# SparkFun_Tri_Axis_Accel_Breakout-H3LIS33.net
KiCad netlist of a schematic drawn in EAGLE
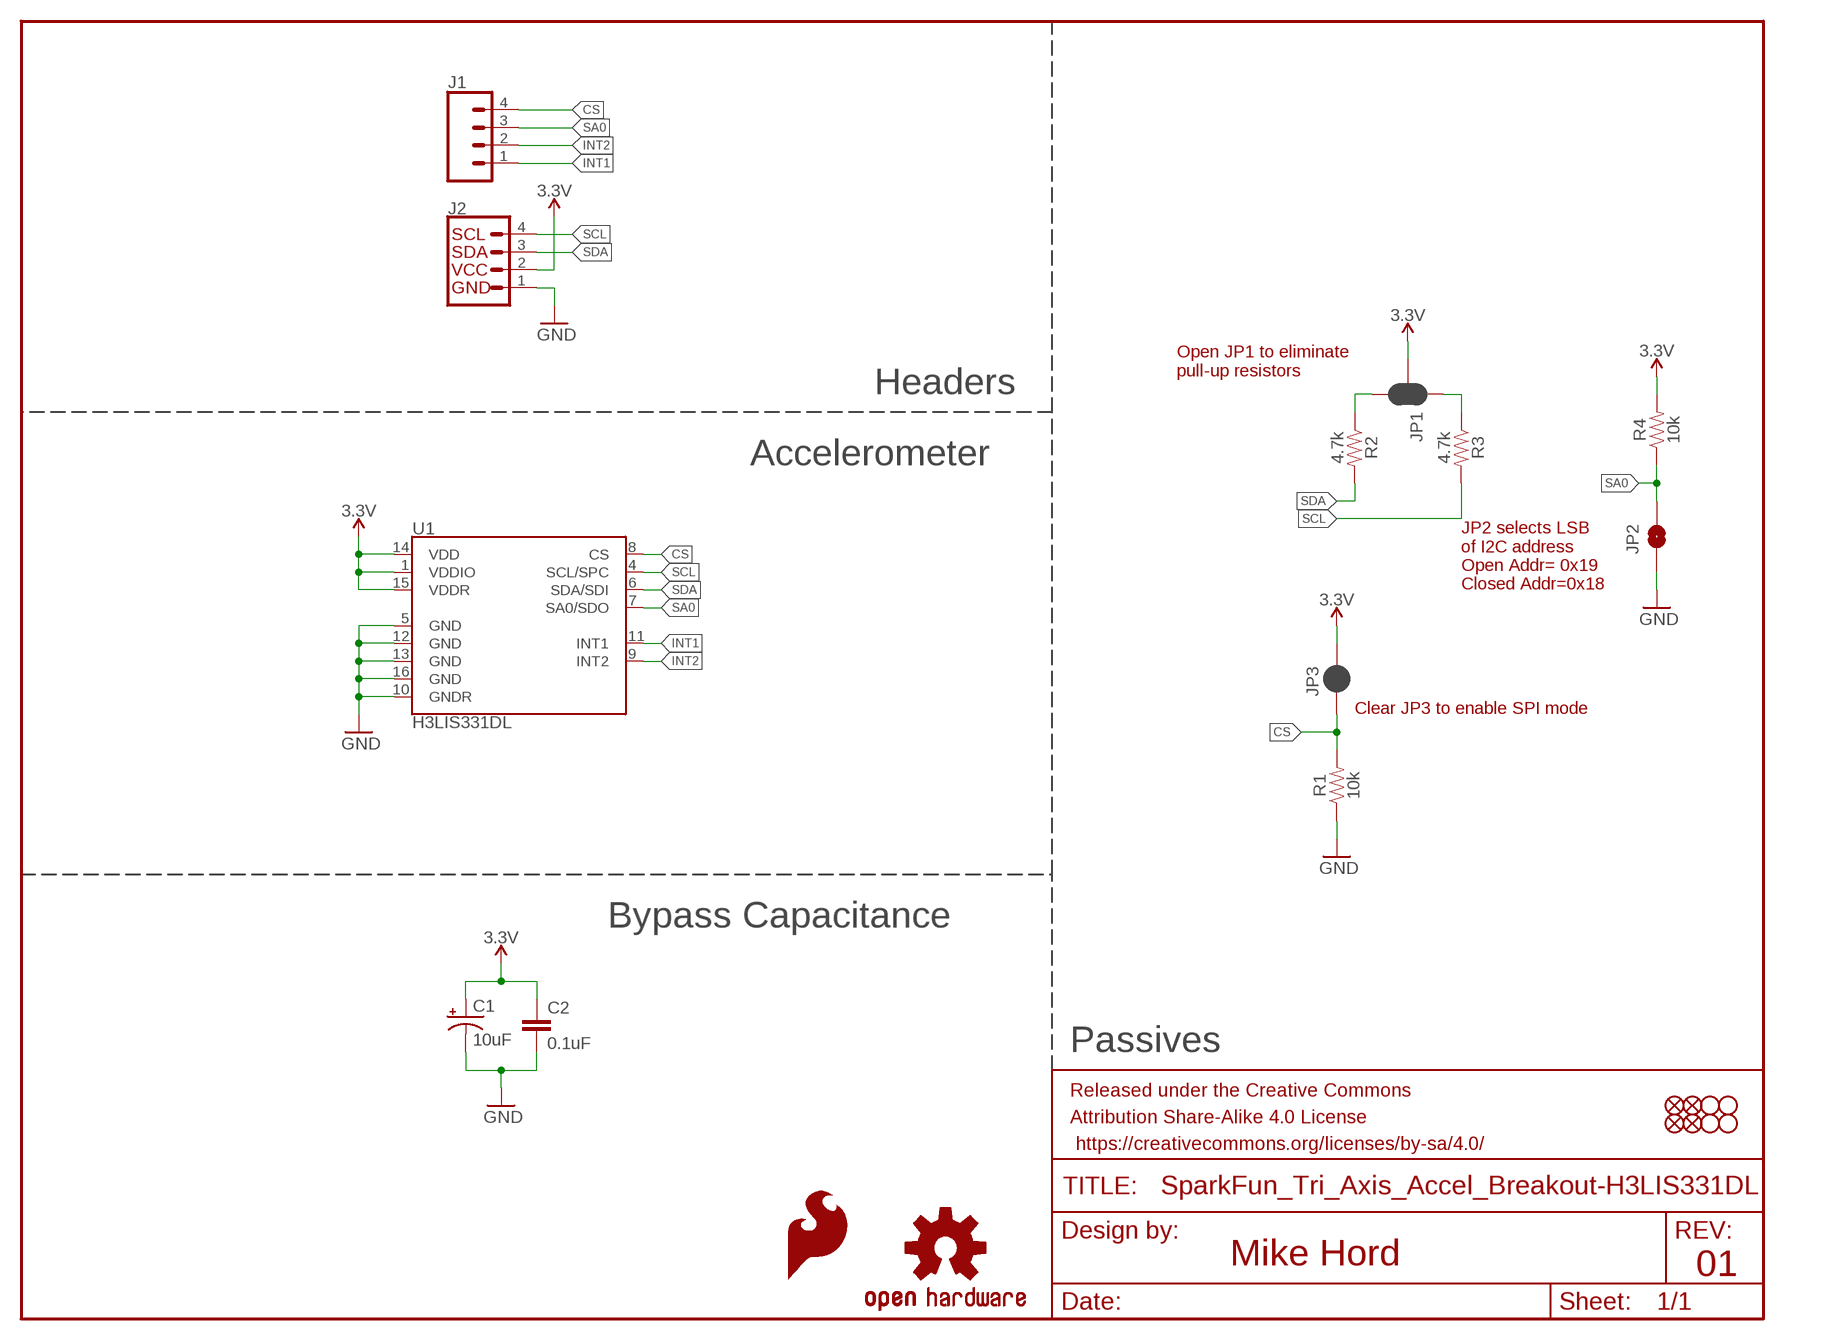
[diagram p0: schematic, sheet 1]

(export (version "E")
  (design (tool "Eeschema 10.0.6"))
  (components
    (comp (ref "C1")
      (value "10uF")
      (footprint "eagle-import:EIA3216")
      (libsource (lib "eagle-import") (part "10UF-POLAR-EIA3216-16V-10%(TANT)"))
    )
    (comp (ref "C2")
      (value "0.1uF")
      (footprint "eagle-import:0603")
      (libsource (lib "eagle-import") (part "0.1UF-0603-25V-5%"))
    )
    (comp (ref "FRAME1")
      (value "FRAME-LETTER")
      (footprint "eagle-import:CREATIVE_COMMONS")
      (libsource (lib "eagle-import") (part "FRAME-LETTER"))
    )
    (comp (ref "J1")
      (value "CONN_04")
      (footprint "eagle-import:1X04")
      (libsource (lib "eagle-import") (part "CONN_04"))
    )
    (comp (ref "J2")
      (value "I2C_STANDARD")
      (footprint "eagle-import:1X04")
      (libsource (lib "eagle-import") (part "I2C_STANDARD"))
    )
    (comp (ref "JP1")
      (value "JUMPER-SMT_3_2-NC_PASTE_NO-SILK")
      (footprint "eagle-import:SMT-JUMPER_3_2-NC_PASTE_NO-SILK")
      (libsource (lib "eagle-import") (part "JUMPER-SMT_3_2-NC_PASTE_NO-SILK"))
    )
    (comp (ref "JP2")
      (value "JUMPER-SMT_2_NO_NO-SILK")
      (footprint "eagle-import:SMT-JUMPER_2_NO_NO-SILK")
      (libsource (lib "eagle-import") (part "JUMPER-SMT_2_NO_NO-SILK"))
    )
    (comp (ref "JP3")
      (value "JUMPER-SMT_2_NC_PASTE_NO-SILK")
      (footprint "eagle-import:SMT-JUMPER_2_NC_PASTE_NO-SILK")
      (libsource (lib "eagle-import") (part "JUMPER-SMT_2_NC_PASTE_NO-SILK"))
    )
    (comp (ref "JP4")
      (value "FIDUCIAL1X2")
      (footprint "eagle-import:FIDUCIAL-1X2")
      (libsource (lib "eagle-import") (part "FIDUCIAL1X2"))
    )
    (comp (ref "JP5")
      (value "FIDUCIAL1X2")
      (footprint "eagle-import:FIDUCIAL-1X2")
      (libsource (lib "eagle-import") (part "FIDUCIAL1X2"))
    )
    (comp (ref "JP6")
      (value "FIDUCIAL1X2")
      (footprint "eagle-import:FIDUCIAL-1X2")
      (libsource (lib "eagle-import") (part "FIDUCIAL1X2"))
    )
    (comp (ref "JP7")
      (value "FIDUCIAL1X2")
      (footprint "eagle-import:FIDUCIAL-1X2")
      (libsource (lib "eagle-import") (part "FIDUCIAL1X2"))
    )
    (comp (ref "JP8")
      (value "STAND-OFF")
      (footprint "eagle-import:STAND-OFF")
      (libsource (lib "eagle-import") (part "STAND-OFF"))
    )
    (comp (ref "JP9")
      (value "STAND-OFF")
      (footprint "eagle-import:STAND-OFF")
      (libsource (lib "eagle-import") (part "STAND-OFF"))
    )
    (comp (ref "JP10")
      (value "STAND-OFF")
      (footprint "eagle-import:STAND-OFF")
      (libsource (lib "eagle-import") (part "STAND-OFF"))
    )
    (comp (ref "JP11")
      (value "STAND-OFF")
      (footprint "eagle-import:STAND-OFF")
      (libsource (lib "eagle-import") (part "STAND-OFF"))
    )
    (comp (ref "LOGO1")
      (value "SFE_LOGO_FLAME.1_INCH")
      (footprint "eagle-import:SFE_LOGO_FLAME_.1")
      (libsource (lib "eagle-import") (part "SFE_LOGO_FLAME.1_INCH"))
    )
    (comp (ref "LOGO2")
      (value "OSHW-LOGOS")
      (footprint "eagle-import:OSHW-LOGO-S")
      (libsource (lib "eagle-import") (part "OSHW-LOGOS"))
    )
    (comp (ref "R1")
      (value "10k")
      (footprint "eagle-import:0603")
      (libsource (lib "eagle-import") (part "10KOHM-0603-1/10W-1%"))
    )
    (comp (ref "R2")
      (value "4.7k")
      (footprint "eagle-import:0603")
      (libsource (lib "eagle-import") (part "4.7KOHM-0603-1/10W-1%"))
    )
    (comp (ref "R3")
      (value "4.7k")
      (footprint "eagle-import:0603")
      (libsource (lib "eagle-import") (part "4.7KOHM-0603-1/10W-1%"))
    )
    (comp (ref "R4")
      (value "10k")
      (footprint "eagle-import:0603")
      (libsource (lib "eagle-import") (part "10KOHM-0603-1/10W-1%"))
    )
    (comp (ref "U1")
      (value "H3LIS331DL")
      (footprint "eagle-import:LGA-16-3X3")
      (libsource (lib "eagle-import") (part "H3LIS331DL"))
    )
  )
  (nets
    (net (code "1") (name "3.3V") (class "Default")
      (node (ref "C1") (pin "+") (pinfunction "+_+") (pintype "passive"))
      (node (ref "C2") (pin "1") (pinfunction "1_1") (pintype "passive"))
      (node (ref "J2") (pin "2") (pinfunction "2_2") (pintype "power_in"))
      (node (ref "JP1") (pin "2") (pinfunction "2_2") (pintype "passive"))
      (node (ref "JP3") (pin "2") (pinfunction "2_2") (pintype "passive"))
      (node (ref "R4") (pin "2") (pinfunction "2_2") (pintype "passive"))
      (node (ref "U1") (pin "1") (pinfunction "VDDIO_1") (pintype "bidirectional"))
      (node (ref "U1") (pin "14") (pinfunction "VDD_14") (pintype "bidirectional"))
      (node (ref "U1") (pin "15") (pinfunction "VDDR_15") (pintype "bidirectional"))
    )
    (net (code "2") (name "CS") (class "Default")
      (node (ref "J1") (pin "4") (pinfunction "4_4") (pintype "passive"))
      (node (ref "JP3") (pin "1") (pinfunction "1_1") (pintype "passive"))
      (node (ref "R1") (pin "2") (pinfunction "2_2") (pintype "passive"))
      (node (ref "U1") (pin "8") (pinfunction "CS_8") (pintype "bidirectional"))
    )
    (net (code "3") (name "GND") (class "Default")
      (node (ref "C1") (pin "-") (pinfunction "-_-") (pintype "passive"))
      (node (ref "C2") (pin "2") (pinfunction "2_2") (pintype "passive"))
      (node (ref "J2") (pin "1") (pinfunction "1_1") (pintype "power_in"))
      (node (ref "JP2") (pin "1") (pinfunction "1_1") (pintype "passive"))
      (node (ref "R1") (pin "1") (pinfunction "1_1") (pintype "passive"))
      (node (ref "U1") (pin "10") (pinfunction "GNDR_10") (pintype "bidirectional"))
      (node (ref "U1") (pin "12") (pinfunction "GND_12") (pintype "bidirectional"))
      (node (ref "U1") (pin "13") (pinfunction "GND_13") (pintype "bidirectional"))
      (node (ref "U1") (pin "16") (pinfunction "GND_16") (pintype "bidirectional"))
      (node (ref "U1") (pin "5") (pinfunction "GND_5") (pintype "bidirectional"))
    )
    (net (code "4") (name "INT1") (class "Default")
      (node (ref "J1") (pin "1") (pinfunction "1_1") (pintype "passive"))
      (node (ref "U1") (pin "11") (pinfunction "INT1_11") (pintype "bidirectional"))
    )
    (net (code "5") (name "INT2") (class "Default")
      (node (ref "J1") (pin "2") (pinfunction "2_2") (pintype "passive"))
      (node (ref "U1") (pin "9") (pinfunction "INT2_9") (pintype "bidirectional"))
    )
    (net (code "6") (name "Net-(JP1-Pad1)") (class "Default")
      (node (ref "JP1") (pin "1") (pinfunction "1_1") (pintype "passive"))
      (node (ref "R3") (pin "1") (pinfunction "1_1") (pintype "passive"))
    )
    (net (code "7") (name "Net-(JP1-Pad3)") (class "Default")
      (node (ref "JP1") (pin "3") (pinfunction "3_3") (pintype "passive"))
      (node (ref "R2") (pin "1") (pinfunction "1_1") (pintype "passive"))
    )
    (net (code "8") (name "SA0") (class "Default")
      (node (ref "J1") (pin "3") (pinfunction "3_3") (pintype "passive"))
      (node (ref "JP2") (pin "2") (pinfunction "2_2") (pintype "passive"))
      (node (ref "R4") (pin "1") (pinfunction "1_1") (pintype "passive"))
      (node (ref "U1") (pin "7") (pinfunction "SA0/SDO_7") (pintype "bidirectional"))
    )
    (net (code "9") (name "SCL") (class "Default")
      (node (ref "J2") (pin "4") (pinfunction "4_4") (pintype "passive"))
      (node (ref "R3") (pin "2") (pinfunction "2_2") (pintype "passive"))
      (node (ref "U1") (pin "4") (pinfunction "SCL/SPC_4") (pintype "bidirectional"))
    )
    (net (code "10") (name "SDA") (class "Default")
      (node (ref "J2") (pin "3") (pinfunction "3_3") (pintype "passive"))
      (node (ref "R2") (pin "2") (pinfunction "2_2") (pintype "passive"))
      (node (ref "U1") (pin "6") (pinfunction "SDA/SDI_6") (pintype "bidirectional"))
    )
  )
)
